# RK3562-PMUIO-OSC-PLL.net
KiCad netlist of a schematic drawn in Altium Designer
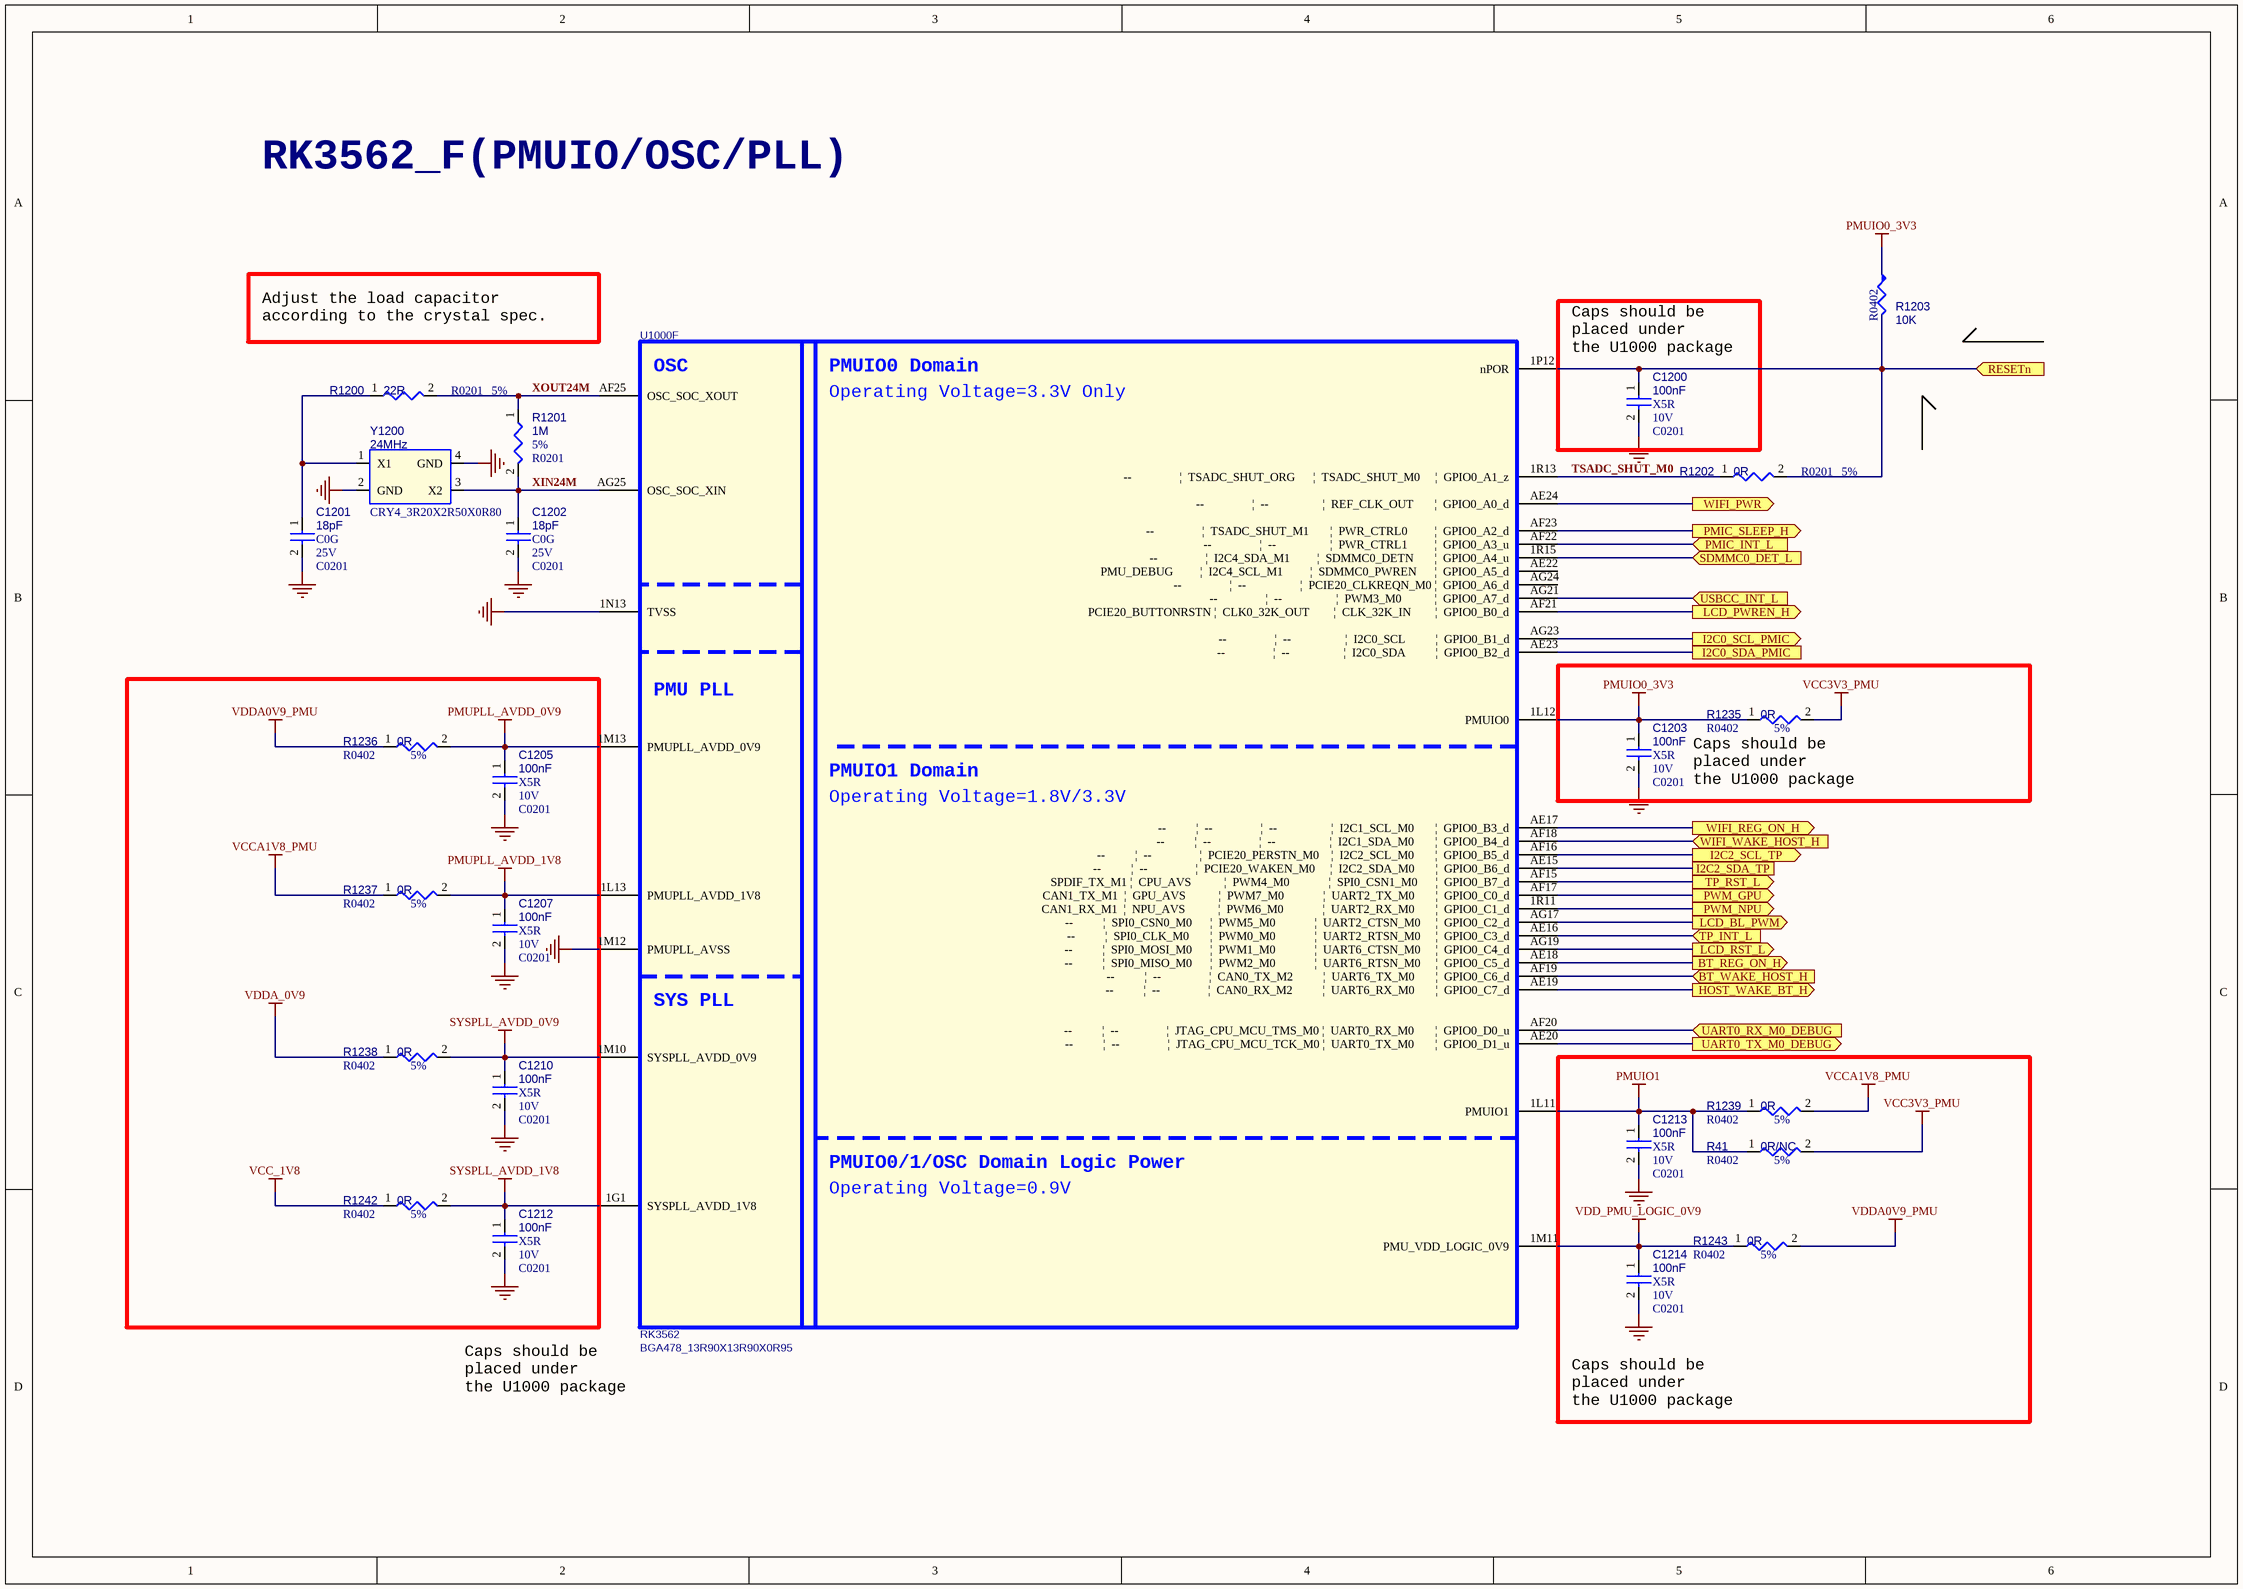
[diagram p0: RK3562-PMUIO-OSC-PLL.SchDoc]

(export (version "E")
  (design (tool "Eeschema 10.0.6"))
  (components
    (comp (ref "C1200")
      (value "100nF")
      (footprint "C0201")
      (description "cap,100.00nF,+/-10%,10V,X5R,C0201")
      (fields
        (field (name "DIELECTRIC") "X5R")
        (field (name "PCB FOOTPRINT") "C0201")
        (field (name "VOLTAGE") "10V")
        (field (name "MANUFACTURER") "TDK")
        (field (name "TOLERANCE") "10%")
        (field (name "CREATED BY") "JJJ")
      )
      (libsource (lib "RK3562_REF") (part "CAP NP"))
    )
    (comp (ref "C1201")
      (value "18pF")
      (footprint "C0201")
      (description "一般用片状陶瓷电容(GRM),cap,18pF,±5%,25V,C0G,C0201")
      (fields
        (field (name "DIELECTRIC") "C0G")
        (field (name "PCB FOOTPRINT") "C0201")
        (field (name "VOLTAGE") "25V")
        (field (name "MANUFACTURER") "murata")
        (field (name "TOLERANCE") "±5%")
        (field (name "CREATED BY") "JJJ")
      )
      (libsource (lib "RK3562_REF") (part "CAP NP"))
    )
    (comp (ref "C1202")
      (value "18pF")
      (footprint "C0201")
      (description "一般用片状陶瓷电容(GRM),cap,18pF,±5%,25V,C0G,C0201")
      (fields
        (field (name "DIELECTRIC") "C0G")
        (field (name "PCB FOOTPRINT") "C0201")
        (field (name "VOLTAGE") "25V")
        (field (name "TOLERANCE") "±5%")
        (field (name "MANUFACTURER") "murata")
        (field (name "CREATED BY") "JJJ")
      )
      (libsource (lib "RK3562_REF") (part "CAP NP"))
    )
    (comp (ref "C1203")
      (value "100nF")
      (footprint "C0201")
      (description "cap,100.00nF,+/-10%,10V,X5R,C0201")
      (fields
        (field (name "DIELECTRIC") "X5R")
        (field (name "PCB FOOTPRINT") "C0201")
        (field (name "VOLTAGE") "10V")
        (field (name "MANUFACTURER") "TDK")
        (field (name "TOLERANCE") "10%")
        (field (name "CREATED BY") "JJJ")
      )
      (libsource (lib "RK3562_REF") (part "CAP NP"))
    )
    (comp (ref "C1205")
      (value "100nF")
      (footprint "C0201")
      (description "cap,100.00nF,+/-10%,10V,X5R,C0201")
      (fields
        (field (name "DIELECTRIC") "X5R")
        (field (name "PCB FOOTPRINT") "C0201")
        (field (name "VOLTAGE") "10V")
        (field (name "TOLERANCE") "10%")
        (field (name "MANUFACTURER") "TDK")
        (field (name "CREATED BY") "JJJ")
      )
      (libsource (lib "RK3562_REF") (part "CAP NP"))
    )
    (comp (ref "C1207")
      (value "100nF")
      (footprint "C0201")
      (description "cap,100.00nF,+/-10%,10V,X5R,C0201")
      (fields
        (field (name "DIELECTRIC") "X5R")
        (field (name "PCB FOOTPRINT") "C0201")
        (field (name "VOLTAGE") "10V")
        (field (name "TOLERANCE") "10%")
        (field (name "MANUFACTURER") "TDK")
        (field (name "CREATED BY") "JJJ")
      )
      (libsource (lib "RK3562_REF") (part "CAP NP"))
    )
    (comp (ref "C1210")
      (value "100nF")
      (footprint "C0201")
      (description "cap,100.00nF,+/-10%,10V,X5R,C0201")
      (fields
        (field (name "DIELECTRIC") "X5R")
        (field (name "PCB FOOTPRINT") "C0201")
        (field (name "VOLTAGE") "10V")
        (field (name "TOLERANCE") "10%")
        (field (name "MANUFACTURER") "TDK")
        (field (name "CREATED BY") "JJJ")
      )
      (libsource (lib "RK3562_REF") (part "CAP NP"))
    )
    (comp (ref "C1212")
      (value "100nF")
      (footprint "C0201")
      (description "cap,100.00nF,+/-10%,10V,X5R,C0201")
      (fields
        (field (name "DIELECTRIC") "X5R")
        (field (name "PCB FOOTPRINT") "C0201")
        (field (name "VOLTAGE") "10V")
        (field (name "MANUFACTURER") "TDK")
        (field (name "TOLERANCE") "10%")
        (field (name "CREATED BY") "JJJ")
      )
      (libsource (lib "RK3562_REF") (part "CAP NP"))
    )
    (comp (ref "C1213")
      (value "100nF")
      (footprint "C0201")
      (description "cap,100.00nF,+/-10%,10V,X5R,C0201")
      (fields
        (field (name "DIELECTRIC") "X5R")
        (field (name "PCB FOOTPRINT") "C0201")
        (field (name "VOLTAGE") "10V")
        (field (name "TOLERANCE") "10%")
        (field (name "MANUFACTURER") "TDK")
        (field (name "CREATED BY") "JJJ")
      )
      (libsource (lib "RK3562_REF") (part "CAP NP"))
    )
    (comp (ref "C1214")
      (value "100nF")
      (footprint "C0201")
      (description "cap,100.00nF,+/-10%,10V,X5R,C0201")
      (fields
        (field (name "DIELECTRIC") "X5R")
        (field (name "PCB FOOTPRINT") "C0201")
        (field (name "VOLTAGE") "10V")
        (field (name "MANUFACTURER") "TDK")
        (field (name "TOLERANCE") "10%")
        (field (name "CREATED BY") "JJJ")
      )
      (libsource (lib "RK3562_REF") (part "CAP NP"))
    )
    (comp (ref "R41")
      (value "0R/NC")
      (footprint "R0402")
      (description "通用厚膜电阻,0R,+/-5%,R0402,1/16W.")
      (fields
        (field (name "TOLERANCE") "5%")
        (field (name "PCB FOOTPRINT") "R0402")
        (field (name "MANUFACTURER") "YAGEO")
        (field (name "CREATED BY") "YTL")
      )
      (libsource (lib "RK3562_REF") (part "RESISTOR"))
    )
    (comp (ref "R1200")
      (value "22R")
      (footprint "R0201")
      (description "通用厚膜电阻,22R,+/-5%,R0201,1/20W.")
      (fields
        (field (name "TOLERANCE") "5%")
        (field (name "PCB FOOTPRINT") "R0201")
        (field (name "MANUFACTURER") "YAGEO")
        (field (name "CREATED BY") "YTL")
      )
      (libsource (lib "RK3562_REF") (part "RESISTOR"))
    )
    (comp (ref "R1201")
      (value "1M")
      (footprint "R0201")
      (description "通用厚膜电阻,1M,+/-5%,R0201,1/20W.")
      (fields
        (field (name "TOLERANCE") "5%")
        (field (name "PCB FOOTPRINT") "R0201")
        (field (name "MANUFACTURER") "YAGEO")
        (field (name "CREATED BY") "YTL")
      )
      (libsource (lib "RK3562_REF") (part "RESISTOR"))
    )
    (comp (ref "R1202")
      (value "0R")
      (footprint "R0201")
      (description "通用厚膜电阻,0R,+/-5%,R0201,1/20W.")
      (fields
        (field (name "TOLERANCE") "5%")
        (field (name "PCB FOOTPRINT") "R0201")
        (field (name "MANUFACTURER") "YAGEO")
        (field (name "CREATED BY") "YTL")
      )
      (libsource (lib "RK3562_REF") (part "RESISTOR"))
    )
    (comp (ref "R1203")
      (value "10K")
      (footprint "R0402")
      (description "通用厚膜电阻,10K,+/-5%,R0402,1/16W.")
      (fields
        (field (name "TOLERANCE") "5%")
        (field (name "PCB FOOTPRINT") "R0402")
        (field (name "MANUFACTURER") "YAGEO")
        (field (name "CREATED BY") "YTL")
      )
      (libsource (lib "RK3562_REF") (part "RESISTOR5"))
    )
    (comp (ref "R1235")
      (value "0R")
      (footprint "R0402")
      (description "通用厚膜电阻,0R,+/-5%,R0402,1/16W.")
      (fields
        (field (name "TOLERANCE") "5%")
        (field (name "PCB FOOTPRINT") "R0402")
        (field (name "MANUFACTURER") "YAGEO")
        (field (name "CREATED BY") "YTL")
      )
      (libsource (lib "RK3562_REF") (part "RESISTOR"))
    )
    (comp (ref "R1236")
      (value "0R")
      (footprint "R0402")
      (description "通用厚膜电阻,0R,+/-5%,R0402,1/16W.")
      (fields
        (field (name "TOLERANCE") "5%")
        (field (name "PCB FOOTPRINT") "R0402")
        (field (name "MANUFACTURER") "YAGEO")
        (field (name "CREATED BY") "YTL")
      )
      (libsource (lib "RK3562_REF") (part "RESISTOR"))
    )
    (comp (ref "R1237")
      (value "0R")
      (footprint "R0402")
      (description "通用厚膜电阻,0R,+/-5%,R0402,1/16W.")
      (fields
        (field (name "TOLERANCE") "5%")
        (field (name "PCB FOOTPRINT") "R0402")
        (field (name "MANUFACTURER") "YAGEO")
        (field (name "CREATED BY") "YTL")
      )
      (libsource (lib "RK3562_REF") (part "RESISTOR"))
    )
    (comp (ref "R1238")
      (value "0R")
      (footprint "R0402")
      (description "通用厚膜电阻,0R,+/-5%,R0402,1/16W.")
      (fields
        (field (name "TOLERANCE") "5%")
        (field (name "PCB FOOTPRINT") "R0402")
        (field (name "MANUFACTURER") "YAGEO")
        (field (name "CREATED BY") "YTL")
      )
      (libsource (lib "RK3562_REF") (part "RESISTOR"))
    )
    (comp (ref "R1239")
      (value "0R")
      (footprint "R0402")
      (description "通用厚膜电阻,0R,+/-5%,R0402,1/16W.")
      (fields
        (field (name "TOLERANCE") "5%")
        (field (name "PCB FOOTPRINT") "R0402")
        (field (name "MANUFACTURER") "YAGEO")
        (field (name "CREATED BY") "YTL")
      )
      (libsource (lib "RK3562_REF") (part "RESISTOR"))
    )
    (comp (ref "R1242")
      (value "0R")
      (footprint "R0402")
      (description "通用厚膜电阻,0R,+/-5%,R0402,1/16W.")
      (fields
        (field (name "TOLERANCE") "5%")
        (field (name "PCB FOOTPRINT") "R0402")
        (field (name "MANUFACTURER") "YAGEO")
        (field (name "CREATED BY") "YTL")
      )
      (libsource (lib "RK3562_REF") (part "RESISTOR"))
    )
    (comp (ref "R1243")
      (value "0R")
      (footprint "R0402")
      (description "通用厚膜电阻,0R,+/-5%,R0402,1/16W.")
      (fields
        (field (name "TOLERANCE") "5%")
        (field (name "PCB FOOTPRINT") "R0402")
        (field (name "MANUFACTURER") "YAGEO")
        (field (name "CREATED BY") "YTL")
      )
      (libsource (lib "RK3562_REF") (part "RESISTOR"))
    )
    (comp (ref "U1000")
      (value "RK3562")
      (footprint "BGA478_13R90X13R90X0R95")
      (description "ROCKCHIP SOC")
      (fields
        (field (name "PCB FOOTPRINT") "BGA478_13R90X13R90X0R95")
        (field (name "MANUFACTURER") "Rockchip (瑞芯微)")
        (field (name "CREATED BY") "JJJ")
      )
      (libsource (lib "RK3562_REF") (part "SOC_RK3562"))
    )
    (comp (ref "Y1200")
      (value "24MHz")
      (footprint "CRY4_3R20X2R50X0R80")
      (description "无源晶振，24M，3225,±10ppm，8pF，Hosonic")
      (fields
        (field (name "PCB FOOTPRINT") "CRY4_3R20X2R50X0R80")
        (field (name "MANUFACTURER") "Hosonic(鸿星电子)")
        (field (name "CREATED BY") "JJJ")
      )
      (libsource (lib "RK3562_REF") (part "CRYSTAL_4P"))
    )
  )
  (nets
    (net (code "1") (name "/BT_REG_ON_H") (class "Default")
      (node (ref "U1000") (pin "AE18") (pinfunction "--__________¦__SPI0_MISO_M0______¦__PWM2_M0_____________¦__UART6_RTSN_M0_____¦__GPIO0_C5_d_AE18") (pintype "passive"))
    )
    (net (code "2") (name "/BT_WAKE_HOST_H") (class "Default")
      (node (ref "U1000") (pin "AF19") (pinfunction "--__________¦__--________________¦__CAN0_TX_M2__________¦__UART6_TX_M0_______¦__GPIO0_C6_d_AF19") (pintype "passive"))
    )
    (net (code "3") (name "/HOST_WAKE_BT_H") (class "Default")
      (node (ref "U1000") (pin "AE19") (pinfunction "--__________¦__--________________¦__CAN0_RX_M2__________¦__UART6_RX_M0_______¦__GPIO0_C7_d_AE19") (pintype "passive"))
    )
    (net (code "4") (name "/I2C0_SCL_PMIC") (class "Default")
      (node (ref "U1000") (pin "AG23") (pinfunction "--________________¦__--__________________¦__I2C0_SCL__________¦__GPIO0_B1_d_AG23") (pintype "passive"))
    )
    (net (code "5") (name "/I2C0_SDA_PMIC") (class "Default")
      (node (ref "U1000") (pin "AE23") (pinfunction "--________________¦__--__________________¦__I2C0_SDA__________¦__GPIO0_B2_d_AE23") (pintype "passive"))
    )
    (net (code "6") (name "/I2C2_SCL_TP") (class "Default")
      (node (ref "U1000") (pin "AF16") (pinfunction "--__________¦__--________________¦__PCIE20_PERSTN_M0____¦__I2C2_SCL_M0_______¦__GPIO0_B5_d_AF16") (pintype "passive"))
    )
    (net (code "7") (name "/I2C2_SDA_TP") (class "Default")
      (node (ref "U1000") (pin "AE15") (pinfunction "--__________¦__--________________¦__PCIE20_WAKEN_M0_____¦__I2C2_SDA_M0_______¦__GPIO0_B6_d_AE15") (pintype "passive"))
    )
    (net (code "8") (name "/LCD_BL_PWM") (class "Default")
      (node (ref "U1000") (pin "AG17") (pinfunction "--__________¦__SPI0_CSN0_M0______¦__PWM5_M0_____________¦__UART2_CTSN_M0_____¦__GPIO0_C2_d_AG17") (pintype "passive"))
    )
    (net (code "9") (name "/LCD_PWREN_H") (class "Default")
      (node (ref "U1000") (pin "AF21") (pinfunction "PCIE20_BUTTONRSTN_¦__CLK0_32K_OUT________¦__CLK_32K_IN________¦__GPIO0_B0_d_AF21") (pintype "passive"))
    )
    (net (code "10") (name "/LCD_RST_L") (class "Default")
      (node (ref "U1000") (pin "AG19") (pinfunction "--__________¦__SPI0_MOSI_M0______¦__PWM1_M0_____________¦__UART6_CTSN_M0_____¦__GPIO0_C4_d_AG19") (pintype "passive"))
    )
    (net (code "11") (name "/PMIC_INT_L") (class "Default")
      (node (ref "U1000") (pin "AF22") (pinfunction "--________________¦__--__________________¦__PWR_CTRL1_________¦__GPIO0_A3_u_AF22") (pintype "passive"))
    )
    (net (code "12") (name "/PMIC_SLEEP_H") (class "Default")
      (node (ref "U1000") (pin "AF23") (pinfunction "--________________¦__TSADC_SHUT_M1_______¦__PWR_CTRL0_________¦__GPIO0_A2_d_AF23") (pintype "passive"))
    )
    (net (code "13") (name "/PWM_GPU") (class "Default")
      (node (ref "U1000") (pin "AF17") (pinfunction "CAN1_TX_M1__¦__GPU_AVS___________¦__PWM7_M0_____________¦__UART2_TX_M0_______¦__GPIO0_C0_d_AF17") (pintype "passive"))
    )
    (net (code "14") (name "/PWM_NPU") (class "Default")
      (node (ref "U1000") (pin "1R11") (pinfunction "CAN1_RX_M1__¦__NPU_AVS___________¦__PWM6_M0_____________¦__UART2_RX_M0_______¦__GPIO0_C1_d_1R11") (pintype "passive"))
    )
    (net (code "15") (name "/RESETn") (class "Default")
      (node (ref "C1200") (pin "1") (pinfunction "1_1") (pintype "passive"))
      (node (ref "R1202") (pin "2") (pinfunction "2_2") (pintype "passive"))
      (node (ref "R1203") (pin "2") (pinfunction "2_2") (pintype "passive"))
      (node (ref "U1000") (pin "1P12") (pinfunction "nPOR_1P12") (pintype "passive"))
    )
    (net (code "16") (name "/SDMMC0_DET_L") (class "Default")
      (node (ref "U1000") (pin "1R15") (pinfunction "--________________¦__I2C4_SDA_M1_________¦__SDMMC0_DETN_______¦__GPIO0_A4_u_1R15") (pintype "passive"))
    )
    (net (code "17") (name "/TP_INT_L") (class "Default")
      (node (ref "U1000") (pin "AE16") (pinfunction "--__________¦__SPI0_CLK_M0_______¦__PWM0_M0_____________¦__UART2_RTSN_M0_____¦__GPIO0_C3_d_AE16") (pintype "passive"))
    )
    (net (code "18") (name "/TP_RST_L") (class "Default")
      (node (ref "U1000") (pin "AF15") (pinfunction "SPDIF_TX_M1_¦__CPU_AVS___________¦__PWM4_M0_____________¦__SPI0_CSN1_M0______¦__GPIO0_B7_d_AF15") (pintype "passive"))
    )
    (net (code "19") (name "/TSADC_SHUT_M0") (class "Default")
      (node (ref "R1202") (pin "1") (pinfunction "1_1") (pintype "passive"))
      (node (ref "U1000") (pin "1R13") (pinfunction "--________________¦__TSADC_SHUT_ORG______¦__TSADC_SHUT_M0_____¦__GPIO0_A1_z_1R13") (pintype "passive"))
    )
    (net (code "20") (name "/UART0_RX_M0_DEBUG") (class "Default")
      (node (ref "U1000") (pin "AF20") (pinfunction "--__________¦__--________________¦__JTAG_CPU_MCU_TMS_M0_¦__UART0_RX_M0_______¦__GPIO0_D0_u_AF20") (pintype "passive"))
    )
    (net (code "21") (name "/UART0_TX_M0_DEBUG") (class "Default")
      (node (ref "U1000") (pin "AE20") (pinfunction "--__________¦__--________________¦__JTAG_CPU_MCU_TCK_M0_¦__UART0_TX_M0_______¦__GPIO0_D1_u_AE20") (pintype "passive"))
    )
    (net (code "22") (name "/USBCC_INT_L") (class "Default")
      (node (ref "U1000") (pin "AG21") (pinfunction "--________________¦__--__________________¦__PWM3_M0___________¦__GPIO0_A7_d_AG21") (pintype "passive"))
    )
    (net (code "23") (name "/WIFI_PWR") (class "Default")
      (node (ref "U1000") (pin "AE24") (pinfunction "--________________¦__--__________________¦__REF_CLK_OUT_______¦__GPIO0_A0_d_AE24") (pintype "passive"))
    )
    (net (code "24") (name "/WIFI_REG_ON_H") (class "Default")
      (node (ref "U1000") (pin "AE17") (pinfunction "--__________¦__--________________¦__--__________________¦__I2C1_SCL_M0_______¦__GPIO0_B3_d_AE17") (pintype "passive"))
    )
    (net (code "25") (name "/WIFI_WAKE_HOST_H") (class "Default")
      (node (ref "U1000") (pin "AF18") (pinfunction "--__________¦__--________________¦__--__________________¦__I2C1_SDA_M0_______¦__GPIO0_B4_d_AF18") (pintype "passive"))
    )
    (net (code "26") (name "/XIN24M") (class "Default")
      (node (ref "C1202") (pin "1") (pinfunction "1_1") (pintype "passive"))
      (node (ref "R1201") (pin "2") (pinfunction "2_2") (pintype "passive"))
      (node (ref "U1000") (pin "AG25") (pinfunction "OSC_SOC_XIN_AG25") (pintype "passive"))
      (node (ref "Y1200") (pin "3") (pinfunction "X2_3") (pintype "passive"))
    )
    (net (code "27") (name "/XOUT24M") (class "Default")
      (node (ref "R1200") (pin "2") (pinfunction "2_2") (pintype "passive"))
      (node (ref "R1201") (pin "1") (pinfunction "1_1") (pintype "passive"))
      (node (ref "U1000") (pin "AF25") (pinfunction "OSC_SOC_XOUT_AF25") (pintype "passive"))
    )
    (net (code "28") (name "GND") (class "Default")
      (node (ref "C1200") (pin "2") (pinfunction "2_2") (pintype "passive"))
      (node (ref "C1201") (pin "2") (pinfunction "2_2") (pintype "passive"))
      (node (ref "C1202") (pin "2") (pinfunction "2_2") (pintype "passive"))
      (node (ref "C1203") (pin "2") (pinfunction "2_2") (pintype "passive"))
      (node (ref "C1205") (pin "2") (pinfunction "2_2") (pintype "passive"))
      (node (ref "C1207") (pin "2") (pinfunction "2_2") (pintype "passive"))
      (node (ref "C1210") (pin "2") (pinfunction "2_2") (pintype "passive"))
      (node (ref "C1212") (pin "2") (pinfunction "2_2") (pintype "passive"))
      (node (ref "C1213") (pin "2") (pinfunction "2_2") (pintype "passive"))
      (node (ref "C1214") (pin "2") (pinfunction "2_2") (pintype "passive"))
      (node (ref "U1000") (pin "1M12") (pinfunction "PMUPLL_AVSS_1M12") (pintype "passive"))
      (node (ref "U1000") (pin "1N13") (pinfunction "TVSS_1N13") (pintype "passive"))
      (node (ref "Y1200") (pin "2") (pinfunction "GND_2") (pintype "power_in"))
      (node (ref "Y1200") (pin "4") (pinfunction "GND_4") (pintype "power_in"))
    )
    (net (code "29") (name "Net-(Y1200-X1)") (class "Default")
      (node (ref "C1201") (pin "1") (pinfunction "1_1") (pintype "passive"))
      (node (ref "R1200") (pin "1") (pinfunction "1_1") (pintype "passive"))
      (node (ref "Y1200") (pin "1") (pinfunction "X1_1") (pintype "passive"))
    )
    (net (code "30") (name "PMUIO0_3V3") (class "Default")
      (node (ref "C1203") (pin "1") (pinfunction "1_1") (pintype "passive"))
      (node (ref "R1203") (pin "1") (pinfunction "1_1") (pintype "passive"))
      (node (ref "R1235") (pin "1") (pinfunction "1_1") (pintype "passive"))
      (node (ref "U1000") (pin "1L12") (pinfunction "PMUIO0_1L12") (pintype "passive"))
    )
    (net (code "31") (name "PMUIO1") (class "Default")
      (node (ref "C1213") (pin "1") (pinfunction "1_1") (pintype "passive"))
      (node (ref "R1239") (pin "1") (pinfunction "1_1") (pintype "passive"))
      (node (ref "R41") (pin "1") (pinfunction "1_1") (pintype "passive"))
      (node (ref "U1000") (pin "1L11") (pinfunction "PMUIO1_1L11") (pintype "passive"))
    )
    (net (code "32") (name "PMUPLL_AVDD_0V9") (class "Default")
      (node (ref "C1205") (pin "1") (pinfunction "1_1") (pintype "passive"))
      (node (ref "R1236") (pin "2") (pinfunction "2_2") (pintype "passive"))
      (node (ref "U1000") (pin "1M13") (pinfunction "PMUPLL_AVDD_0V9_1M13") (pintype "passive"))
    )
    (net (code "33") (name "PMUPLL_AVDD_1V8") (class "Default")
      (node (ref "C1207") (pin "1") (pinfunction "1_1") (pintype "passive"))
      (node (ref "R1237") (pin "2") (pinfunction "2_2") (pintype "passive"))
      (node (ref "U1000") (pin "1L13") (pinfunction "PMUPLL_AVDD_1V8_1L13") (pintype "passive"))
    )
    (net (code "34") (name "SYSPLL_AVDD_0V9") (class "Default")
      (node (ref "C1210") (pin "1") (pinfunction "1_1") (pintype "passive"))
      (node (ref "R1238") (pin "2") (pinfunction "2_2") (pintype "passive"))
      (node (ref "U1000") (pin "1M10") (pinfunction "SYSPLL_AVDD_0V9_1M10") (pintype "passive"))
    )
    (net (code "35") (name "SYSPLL_AVDD_1V8") (class "Default")
      (node (ref "C1212") (pin "1") (pinfunction "1_1") (pintype "passive"))
      (node (ref "R1242") (pin "2") (pinfunction "2_2") (pintype "passive"))
      (node (ref "U1000") (pin "1G1") (pinfunction "SYSPLL_AVDD_1V8_1G1") (pintype "passive"))
    )
    (net (code "36") (name "VCC3V3_PMU") (class "Default")
      (node (ref "R1235") (pin "2") (pinfunction "2_2") (pintype "passive"))
      (node (ref "R41") (pin "2") (pinfunction "2_2") (pintype "passive"))
    )
    (net (code "37") (name "VCCA1V8_PMU") (class "Default")
      (node (ref "R1237") (pin "1") (pinfunction "1_1") (pintype "passive"))
      (node (ref "R1239") (pin "2") (pinfunction "2_2") (pintype "passive"))
    )
    (net (code "38") (name "VCC_1V8") (class "Default")
      (node (ref "R1242") (pin "1") (pinfunction "1_1") (pintype "passive"))
    )
    (net (code "39") (name "VDDA0V9_PMU") (class "Default")
      (node (ref "R1236") (pin "1") (pinfunction "1_1") (pintype "passive"))
      (node (ref "R1243") (pin "2") (pinfunction "2_2") (pintype "passive"))
    )
    (net (code "40") (name "VDDA_0V9") (class "Default")
      (node (ref "R1238") (pin "1") (pinfunction "1_1") (pintype "passive"))
    )
    (net (code "41") (name "VDD_PMU_LOGIC_0V9") (class "Default")
      (node (ref "C1214") (pin "1") (pinfunction "1_1") (pintype "passive"))
      (node (ref "R1243") (pin "1") (pinfunction "1_1") (pintype "passive"))
      (node (ref "U1000") (pin "1M11") (pinfunction "PMU_VDD_LOGIC_0V9_1M11") (pintype "passive"))
    )
    (net (code "42") (name "unconnected-(U1000F---________________¦__--__________________¦__PCIE20_CLKREQN_M0_¦__GPIO0_A6_d-PadAG24)") (class "Default")
      (node (ref "U1000") (pin "AG24") (pinfunction "--________________¦__--__________________¦__PCIE20_CLKREQN_M0_¦__GPIO0_A6_d_AG24") (pintype "passive"))
    )
    (net (code "43") (name "unconnected-(U1000F-PMU_DEBUG_________¦__I2C4_SCL_M1_________¦__SDMMC0_PWREN______¦__GPIO0_A5_d-PadAE22)") (class "Default")
      (node (ref "U1000") (pin "AE22") (pinfunction "PMU_DEBUG_________¦__I2C4_SCL_M1_________¦__SDMMC0_PWREN______¦__GPIO0_A5_d_AE22") (pintype "passive"))
    )
  )
)
